# snullv5.net
KiCad netlist of a schematic drawn in EAGLE
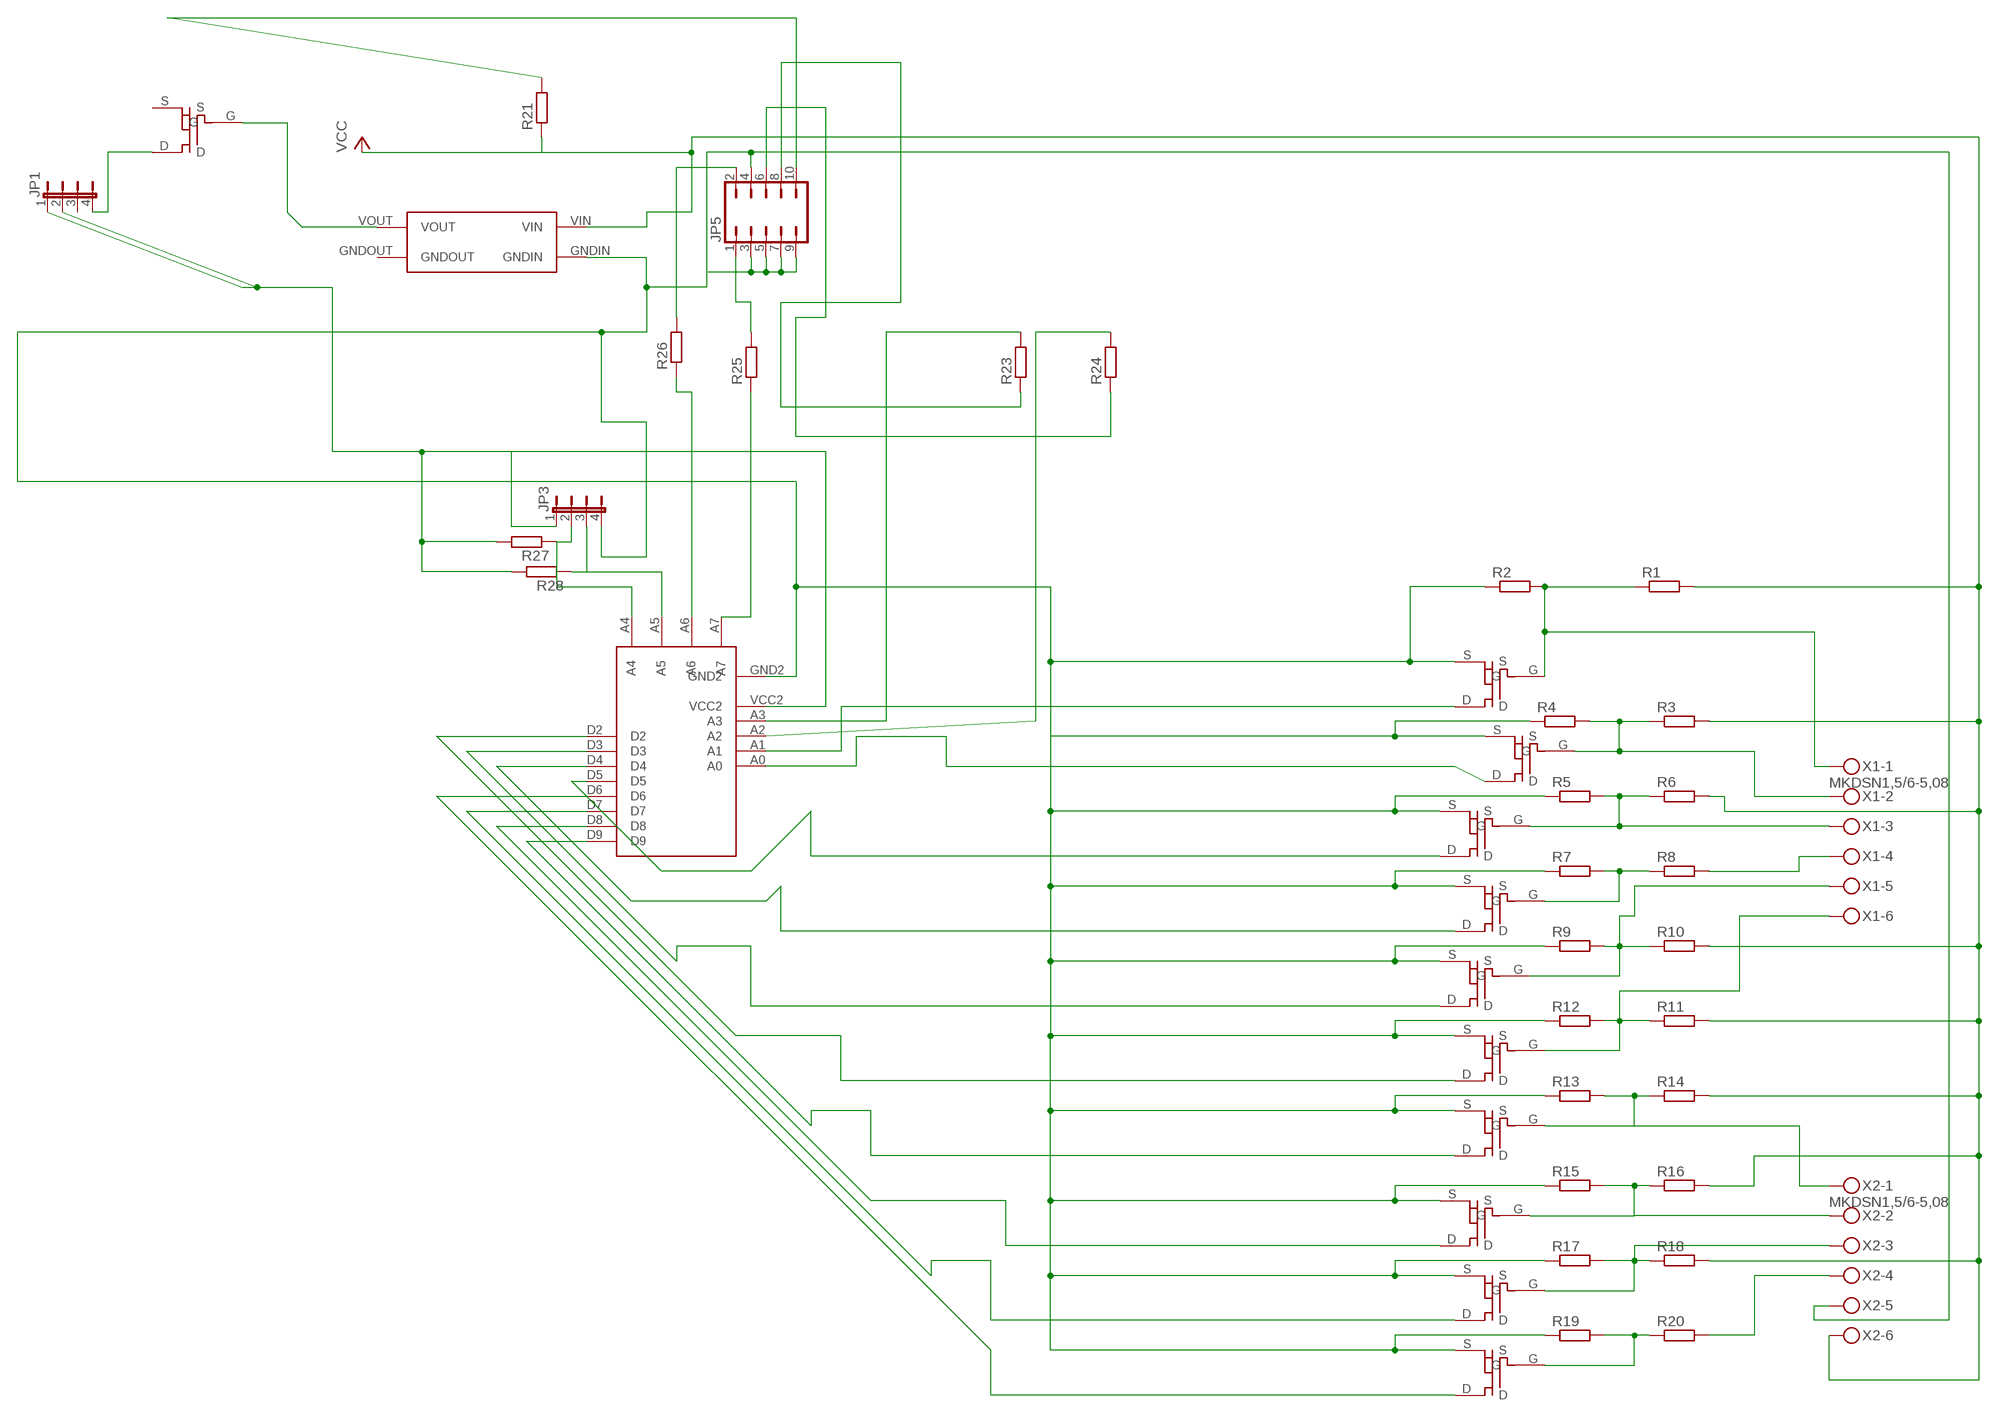
[diagram p0: schematic, sheet 1]

(export (version "E")
  (design (tool "Eeschema 10.0.6"))
  (components
    (comp (ref "JP1")
      (value "JP4E")
      (footprint "eagle-import:JP4")
      (libsource (lib "eagle-import") (part "JP4E"))
    )
    (comp (ref "JP3")
      (value "JP4E")
      (footprint "eagle-import:JP4")
      (libsource (lib "eagle-import") (part "JP4E"))
    )
    (comp (ref "JP5")
      (value "JP5Q")
      (footprint "eagle-import:JP5Q")
      (libsource (lib "eagle-import") (part "JP5Q"))
    )
    (comp (ref "R1")
      (value "R-EU_R0805")
      (footprint "eagle-import:R0805")
      (libsource (lib "eagle-import") (part "R-EU_R0805"))
    )
    (comp (ref "R2")
      (value "R-EU_R0805")
      (footprint "eagle-import:R0805")
      (libsource (lib "eagle-import") (part "R-EU_R0805"))
    )
    (comp (ref "R3")
      (value "R-EU_R0805")
      (footprint "eagle-import:R0805")
      (libsource (lib "eagle-import") (part "R-EU_R0805"))
    )
    (comp (ref "R4")
      (value "R-EU_R0805")
      (footprint "eagle-import:R0805")
      (libsource (lib "eagle-import") (part "R-EU_R0805"))
    )
    (comp (ref "R5")
      (value "R-EU_R0805")
      (footprint "eagle-import:R0805")
      (libsource (lib "eagle-import") (part "R-EU_R0805"))
    )
    (comp (ref "R6")
      (value "R-EU_R0805")
      (footprint "eagle-import:R0805")
      (libsource (lib "eagle-import") (part "R-EU_R0805"))
    )
    (comp (ref "R7")
      (value "R-EU_R0805")
      (footprint "eagle-import:R0805")
      (libsource (lib "eagle-import") (part "R-EU_R0805"))
    )
    (comp (ref "R8")
      (value "R-EU_R0805")
      (footprint "eagle-import:R0805")
      (libsource (lib "eagle-import") (part "R-EU_R0805"))
    )
    (comp (ref "R9")
      (value "R-EU_R0805")
      (footprint "eagle-import:R0805")
      (libsource (lib "eagle-import") (part "R-EU_R0805"))
    )
    (comp (ref "R10")
      (value "R-EU_R0805")
      (footprint "eagle-import:R0805")
      (libsource (lib "eagle-import") (part "R-EU_R0805"))
    )
    (comp (ref "R11")
      (value "R-EU_R0805")
      (footprint "eagle-import:R0805")
      (libsource (lib "eagle-import") (part "R-EU_R0805"))
    )
    (comp (ref "R12")
      (value "R-EU_R0805")
      (footprint "eagle-import:R0805")
      (libsource (lib "eagle-import") (part "R-EU_R0805"))
    )
    (comp (ref "R13")
      (value "R-EU_R0805")
      (footprint "eagle-import:R0805")
      (libsource (lib "eagle-import") (part "R-EU_R0805"))
    )
    (comp (ref "R14")
      (value "R-EU_R0805")
      (footprint "eagle-import:R0805")
      (libsource (lib "eagle-import") (part "R-EU_R0805"))
    )
    (comp (ref "R15")
      (value "R-EU_R0805")
      (footprint "eagle-import:R0805")
      (libsource (lib "eagle-import") (part "R-EU_R0805"))
    )
    (comp (ref "R16")
      (value "R-EU_R0805")
      (footprint "eagle-import:R0805")
      (libsource (lib "eagle-import") (part "R-EU_R0805"))
    )
    (comp (ref "R17")
      (value "R-EU_R0805")
      (footprint "eagle-import:R0805")
      (libsource (lib "eagle-import") (part "R-EU_R0805"))
    )
    (comp (ref "R18")
      (value "R-EU_R0805")
      (footprint "eagle-import:R0805")
      (libsource (lib "eagle-import") (part "R-EU_R0805"))
    )
    (comp (ref "R19")
      (value "R-EU_R0805")
      (footprint "eagle-import:R0805")
      (libsource (lib "eagle-import") (part "R-EU_R0805"))
    )
    (comp (ref "R20")
      (value "R-EU_R0805")
      (footprint "eagle-import:R0805")
      (libsource (lib "eagle-import") (part "R-EU_R0805"))
    )
    (comp (ref "R21")
      (value "R-EU_R0805")
      (footprint "eagle-import:R0805")
      (libsource (lib "eagle-import") (part "R-EU_R0805"))
    )
    (comp (ref "R23")
      (value "R-EU_R0805")
      (footprint "eagle-import:R0805")
      (libsource (lib "eagle-import") (part "R-EU_R0805"))
    )
    (comp (ref "R24")
      (value "R-EU_R0805")
      (footprint "eagle-import:R0805")
      (libsource (lib "eagle-import") (part "R-EU_R0805"))
    )
    (comp (ref "R25")
      (value "R-EU_R0805")
      (footprint "eagle-import:R0805")
      (libsource (lib "eagle-import") (part "R-EU_R0805"))
    )
    (comp (ref "R26")
      (value "R-EU_R0805")
      (footprint "eagle-import:R0805")
      (libsource (lib "eagle-import") (part "R-EU_R0805"))
    )
    (comp (ref "R27")
      (value "R-EU_R0805")
      (footprint "eagle-import:R0805")
      (libsource (lib "eagle-import") (part "R-EU_R0805"))
    )
    (comp (ref "R28")
      (value "R-EU_R0805")
      (footprint "eagle-import:R0805")
      (libsource (lib "eagle-import") (part "R-EU_R0805"))
    )
    (comp (ref "U$1")
      (value "ARDUINOPROMINIREDUCED")
      (footprint "eagle-import:ARDUINOPROMINIREDUCED")
      (libsource (lib "eagle-import") (part "ARDUINOPROMINIREDUCED"))
    )
    (comp (ref "U$2")
      (value "VREGMODULE")
      (footprint "eagle-import:VREGMODULE")
      (libsource (lib "eagle-import") (part "VREGMODULE"))
    )
    (comp (ref "U$3")
      (value "MOSFET-TO236")
      (footprint "eagle-import:MOSFET-TO236")
      (libsource (lib "eagle-import") (part "MOSFET-TO236"))
    )
    (comp (ref "U$4")
      (value "MOSFET-TO236")
      (footprint "eagle-import:MOSFET-TO236")
      (libsource (lib "eagle-import") (part "MOSFET-TO236"))
    )
    (comp (ref "U$5")
      (value "MOSFET-TO236")
      (footprint "eagle-import:MOSFET-TO236")
      (libsource (lib "eagle-import") (part "MOSFET-TO236"))
    )
    (comp (ref "U$6")
      (value "MOSFET-TO236")
      (footprint "eagle-import:MOSFET-TO236")
      (libsource (lib "eagle-import") (part "MOSFET-TO236"))
    )
    (comp (ref "U$7")
      (value "MOSFET-TO236")
      (footprint "eagle-import:MOSFET-TO236")
      (libsource (lib "eagle-import") (part "MOSFET-TO236"))
    )
    (comp (ref "U$8")
      (value "MOSFET-TO236")
      (footprint "eagle-import:MOSFET-TO236")
      (libsource (lib "eagle-import") (part "MOSFET-TO236"))
    )
    (comp (ref "U$9")
      (value "MOSFET-TO236")
      (footprint "eagle-import:MOSFET-TO236")
      (libsource (lib "eagle-import") (part "MOSFET-TO236"))
    )
    (comp (ref "U$10")
      (value "MOSFET-TO236")
      (footprint "eagle-import:MOSFET-TO236")
      (libsource (lib "eagle-import") (part "MOSFET-TO236"))
    )
    (comp (ref "U$11")
      (value "MOSFET-TO236")
      (footprint "eagle-import:MOSFET-TO236")
      (libsource (lib "eagle-import") (part "MOSFET-TO236"))
    )
    (comp (ref "U$12")
      (value "MOSFET-TO236")
      (footprint "eagle-import:MOSFET-TO236")
      (libsource (lib "eagle-import") (part "MOSFET-TO236"))
    )
    (comp (ref "U$13")
      (value "MOSFET-TO236")
      (footprint "eagle-import:MOSFET-TO236")
      (libsource (lib "eagle-import") (part "MOSFET-TO236"))
    )
    (comp (ref "X1")
      (value "MKDSN1,5/6-5,08")
      (footprint "eagle-import:MKDSN1,5_6-5,08")
      (libsource (lib "eagle-import") (part "MKDSN1,5/6-5,08"))
    )
    (comp (ref "X2")
      (value "MKDSN1,5/6-5,08")
      (footprint "eagle-import:MKDSN1,5_6-5,08")
      (libsource (lib "eagle-import") (part "MKDSN1,5/6-5,08"))
    )
  )
  (nets
    (net (code "1") (name "Net-(JP1-Pad1)") (class "Default")
      (node (ref "JP1") (pin "1") (pinfunction "1_1") (pintype "passive"))
      (node (ref "JP1") (pin "2") (pinfunction "2_2") (pintype "passive"))
      (node (ref "JP3") (pin "1") (pinfunction "1_1") (pintype "passive"))
      (node (ref "R27") (pin "2") (pinfunction "2_2") (pintype "passive"))
      (node (ref "R28") (pin "2") (pinfunction "2_2") (pintype "passive"))
      (node (ref "U$1") (pin "VCC2") (pinfunction "VCC2_VCC2") (pintype "bidirectional"))
    )
    (net (code "2") (name "Net-(JP1-Pad4)") (class "Default")
      (node (ref "JP1") (pin "4") (pinfunction "4_4") (pintype "passive"))
      (node (ref "U$13") (pin "D") (pinfunction "D_D") (pintype "bidirectional"))
    )
    (net (code "3") (name "Net-(JP3-Pad2)") (class "Default")
      (node (ref "JP3") (pin "2") (pinfunction "2_2") (pintype "passive"))
      (node (ref "R27") (pin "1") (pinfunction "1_1") (pintype "passive"))
      (node (ref "U$1") (pin "A4") (pinfunction "A4_A4") (pintype "bidirectional"))
    )
    (net (code "4") (name "Net-(JP3-Pad3)") (class "Default")
      (node (ref "JP3") (pin "3") (pinfunction "3_3") (pintype "passive"))
      (node (ref "R28") (pin "1") (pinfunction "1_1") (pintype "passive"))
      (node (ref "U$1") (pin "A5") (pinfunction "A5_A5") (pintype "bidirectional"))
    )
    (net (code "5") (name "Net-(JP5-Pad1)") (class "Default")
      (node (ref "JP5") (pin "1") (pinfunction "1_1") (pintype "passive"))
      (node (ref "R25") (pin "2") (pinfunction "2_2") (pintype "passive"))
    )
    (net (code "6") (name "Net-(JP5-Pad2)") (class "Default")
      (node (ref "JP5") (pin "2") (pinfunction "2_2") (pintype "passive"))
      (node (ref "R26") (pin "2") (pinfunction "2_2") (pintype "passive"))
    )
    (net (code "7") (name "Net-(JP5-Pad6)") (class "Default")
      (node (ref "JP5") (pin "6") (pinfunction "6_6") (pintype "passive"))
      (node (ref "R24") (pin "1") (pinfunction "1_1") (pintype "passive"))
    )
    (net (code "8") (name "Net-(JP5-Pad8)") (class "Default")
      (node (ref "JP5") (pin "8") (pinfunction "8_8") (pintype "passive"))
      (node (ref "R23") (pin "1") (pinfunction "1_1") (pintype "passive"))
    )
    (net (code "9") (name "Net-(JP5-Pad10)") (class "Default")
      (node (ref "JP5") (pin "10") (pinfunction "10_10") (pintype "passive"))
      (node (ref "R21") (pin "2") (pinfunction "2_2") (pintype "passive"))
    )
    (net (code "10") (name "Net-(R7-Pad2)") (class "Default")
      (node (ref "R7") (pin "2") (pinfunction "2_2") (pintype "passive"))
      (node (ref "R8") (pin "1") (pinfunction "1_1") (pintype "passive"))
      (node (ref "U$6") (pin "G") (pinfunction "G_G") (pintype "bidirectional"))
    )
    (net (code "11") (name "Net-(R19-Pad2)") (class "Default")
      (node (ref "R19") (pin "2") (pinfunction "2_2") (pintype "passive"))
      (node (ref "R20") (pin "1") (pinfunction "1_1") (pintype "passive"))
      (node (ref "U$12") (pin "G") (pinfunction "G_G") (pintype "bidirectional"))
    )
    (net (code "12") (name "Net-(R23-Pad2)") (class "Default")
      (node (ref "R23") (pin "2") (pinfunction "2_2") (pintype "passive"))
      (node (ref "U$1") (pin "A3") (pinfunction "A3_A3") (pintype "bidirectional"))
    )
    (net (code "13") (name "Net-(R24-Pad2)") (class "Default")
      (node (ref "R24") (pin "2") (pinfunction "2_2") (pintype "passive"))
      (node (ref "U$1") (pin "A2") (pinfunction "A2_A2") (pintype "bidirectional"))
    )
    (net (code "14") (name "Net-(R25-Pad1)") (class "Default")
      (node (ref "R25") (pin "1") (pinfunction "1_1") (pintype "passive"))
      (node (ref "U$1") (pin "A7") (pinfunction "A7_A7") (pintype "bidirectional"))
    )
    (net (code "15") (name "Net-(R26-Pad1)") (class "Default")
      (node (ref "R26") (pin "1") (pinfunction "1_1") (pintype "passive"))
      (node (ref "U$1") (pin "A6") (pinfunction "A6_A6") (pintype "bidirectional"))
    )
    (net (code "16") (name "Net-(U$1-PadA0)") (class "Default")
      (node (ref "U$1") (pin "A0") (pinfunction "A0_A0") (pintype "bidirectional"))
      (node (ref "U$4") (pin "D") (pinfunction "D_D") (pintype "bidirectional"))
    )
    (net (code "17") (name "Net-(U$1-PadA1)") (class "Default")
      (node (ref "U$1") (pin "A1") (pinfunction "A1_A1") (pintype "bidirectional"))
      (node (ref "U$3") (pin "D") (pinfunction "D_D") (pintype "bidirectional"))
    )
    (net (code "18") (name "Net-(U$1-PadD2)") (class "Default")
      (node (ref "U$1") (pin "D2") (pinfunction "D2_D2") (pintype "bidirectional"))
      (node (ref "U$8") (pin "D") (pinfunction "D_D") (pintype "bidirectional"))
    )
    (net (code "19") (name "Net-(U$1-PadD3)") (class "Default")
      (node (ref "U$1") (pin "D3") (pinfunction "D3_D3") (pintype "bidirectional"))
      (node (ref "U$7") (pin "D") (pinfunction "D_D") (pintype "bidirectional"))
    )
    (net (code "20") (name "Net-(U$1-PadD4)") (class "Default")
      (node (ref "U$1") (pin "D4") (pinfunction "D4_D4") (pintype "bidirectional"))
      (node (ref "U$6") (pin "D") (pinfunction "D_D") (pintype "bidirectional"))
    )
    (net (code "21") (name "Net-(U$1-PadD5)") (class "Default")
      (node (ref "U$1") (pin "D5") (pinfunction "D5_D5") (pintype "bidirectional"))
      (node (ref "U$5") (pin "D") (pinfunction "D_D") (pintype "bidirectional"))
    )
    (net (code "22") (name "Net-(U$1-PadD6)") (class "Default")
      (node (ref "U$1") (pin "D6") (pinfunction "D6_D6") (pintype "bidirectional"))
      (node (ref "U$12") (pin "D") (pinfunction "D_D") (pintype "bidirectional"))
    )
    (net (code "23") (name "Net-(U$1-PadD7)") (class "Default")
      (node (ref "U$1") (pin "D7") (pinfunction "D7_D7") (pintype "bidirectional"))
      (node (ref "U$11") (pin "D") (pinfunction "D_D") (pintype "bidirectional"))
    )
    (net (code "24") (name "Net-(U$1-PadD8)") (class "Default")
      (node (ref "U$1") (pin "D8") (pinfunction "D8_D8") (pintype "bidirectional"))
      (node (ref "U$10") (pin "D") (pinfunction "D_D") (pintype "bidirectional"))
    )
    (net (code "25") (name "Net-(U$1-PadD9)") (class "Default")
      (node (ref "U$1") (pin "D9") (pinfunction "D9_D9") (pintype "bidirectional"))
      (node (ref "U$9") (pin "D") (pinfunction "D_D") (pintype "bidirectional"))
    )
    (net (code "26") (name "Net-(U$13-PadG)") (class "Default")
      (node (ref "U$13") (pin "G") (pinfunction "G_G") (pintype "bidirectional"))
      (node (ref "U$2") (pin "VOUT") (pinfunction "VOUT_VOUT") (pintype "bidirectional"))
    )
    (net (code "27") (name "Net-(X1A-KL)") (class "Default")
      (node (ref "R1") (pin "1") (pinfunction "1_1") (pintype "passive"))
      (node (ref "R2") (pin "2") (pinfunction "2_2") (pintype "passive"))
      (node (ref "U$3") (pin "G") (pinfunction "G_G") (pintype "bidirectional"))
      (node (ref "X1") (pin "1") (pinfunction "KL_1") (pintype "passive"))
    )
    (net (code "28") (name "Net-(X1B-KL)") (class "Default")
      (node (ref "R3") (pin "1") (pinfunction "1_1") (pintype "passive"))
      (node (ref "R4") (pin "2") (pinfunction "2_2") (pintype "passive"))
      (node (ref "U$4") (pin "G") (pinfunction "G_G") (pintype "bidirectional"))
      (node (ref "X1") (pin "2") (pinfunction "KL_2") (pintype "passive"))
    )
    (net (code "29") (name "Net-(X1C-KL)") (class "Default")
      (node (ref "R5") (pin "2") (pinfunction "2_2") (pintype "passive"))
      (node (ref "R6") (pin "1") (pinfunction "1_1") (pintype "passive"))
      (node (ref "U$5") (pin "G") (pinfunction "G_G") (pintype "bidirectional"))
      (node (ref "X1") (pin "3") (pinfunction "KL_3") (pintype "passive"))
    )
    (net (code "30") (name "Net-(X1D-KL)") (class "Default")
      (node (ref "R8") (pin "2") (pinfunction "2_2") (pintype "passive"))
      (node (ref "X1") (pin "4") (pinfunction "KL_4") (pintype "passive"))
    )
    (net (code "31") (name "Net-(X1E-KL)") (class "Default")
      (node (ref "R10") (pin "1") (pinfunction "1_1") (pintype "passive"))
      (node (ref "R9") (pin "2") (pinfunction "2_2") (pintype "passive"))
      (node (ref "U$7") (pin "G") (pinfunction "G_G") (pintype "bidirectional"))
      (node (ref "X1") (pin "5") (pinfunction "KL_5") (pintype "passive"))
    )
    (net (code "32") (name "Net-(X1F-KL)") (class "Default")
      (node (ref "R11") (pin "1") (pinfunction "1_1") (pintype "passive"))
      (node (ref "R12") (pin "2") (pinfunction "2_2") (pintype "passive"))
      (node (ref "U$8") (pin "G") (pinfunction "G_G") (pintype "bidirectional"))
      (node (ref "X1") (pin "6") (pinfunction "KL_6") (pintype "passive"))
    )
    (net (code "33") (name "Net-(X2A-KL)") (class "Default")
      (node (ref "R13") (pin "2") (pinfunction "2_2") (pintype "passive"))
      (node (ref "R14") (pin "1") (pinfunction "1_1") (pintype "passive"))
      (node (ref "U$9") (pin "G") (pinfunction "G_G") (pintype "bidirectional"))
      (node (ref "X2") (pin "1") (pinfunction "KL_1") (pintype "passive"))
    )
    (net (code "34") (name "Net-(X2B-KL)") (class "Default")
      (node (ref "R15") (pin "2") (pinfunction "2_2") (pintype "passive"))
      (node (ref "R16") (pin "1") (pinfunction "1_1") (pintype "passive"))
      (node (ref "U$10") (pin "G") (pinfunction "G_G") (pintype "bidirectional"))
      (node (ref "X2") (pin "2") (pinfunction "KL_2") (pintype "passive"))
    )
    (net (code "35") (name "Net-(X2C-KL)") (class "Default")
      (node (ref "R17") (pin "2") (pinfunction "2_2") (pintype "passive"))
      (node (ref "R18") (pin "1") (pinfunction "1_1") (pintype "passive"))
      (node (ref "U$11") (pin "G") (pinfunction "G_G") (pintype "bidirectional"))
      (node (ref "X2") (pin "3") (pinfunction "KL_3") (pintype "passive"))
    )
    (net (code "36") (name "Net-(X2D-KL)") (class "Default")
      (node (ref "R20") (pin "2") (pinfunction "2_2") (pintype "passive"))
      (node (ref "X2") (pin "4") (pinfunction "KL_4") (pintype "passive"))
    )
    (net (code "37") (name "Net-(X2E-KL)") (class "Default")
      (node (ref "JP3") (pin "4") (pinfunction "4_4") (pintype "passive"))
      (node (ref "JP5") (pin "3") (pinfunction "3_3") (pintype "passive"))
      (node (ref "JP5") (pin "4") (pinfunction "4_4") (pintype "passive"))
      (node (ref "JP5") (pin "5") (pinfunction "5_5") (pintype "passive"))
      (node (ref "JP5") (pin "7") (pinfunction "7_7") (pintype "passive"))
      (node (ref "JP5") (pin "9") (pinfunction "9_9") (pintype "passive"))
      (node (ref "R12") (pin "1") (pinfunction "1_1") (pintype "passive"))
      (node (ref "R13") (pin "1") (pinfunction "1_1") (pintype "passive"))
      (node (ref "R15") (pin "1") (pinfunction "1_1") (pintype "passive"))
      (node (ref "R17") (pin "1") (pinfunction "1_1") (pintype "passive"))
      (node (ref "R19") (pin "1") (pinfunction "1_1") (pintype "passive"))
      (node (ref "R2") (pin "1") (pinfunction "1_1") (pintype "passive"))
      (node (ref "R4") (pin "1") (pinfunction "1_1") (pintype "passive"))
      (node (ref "R5") (pin "1") (pinfunction "1_1") (pintype "passive"))
      (node (ref "R7") (pin "1") (pinfunction "1_1") (pintype "passive"))
      (node (ref "R9") (pin "1") (pinfunction "1_1") (pintype "passive"))
      (node (ref "U$1") (pin "GND2") (pinfunction "GND2_GND2") (pintype "bidirectional"))
      (node (ref "U$10") (pin "S") (pinfunction "S_S") (pintype "bidirectional"))
      (node (ref "U$11") (pin "S") (pinfunction "S_S") (pintype "bidirectional"))
      (node (ref "U$12") (pin "S") (pinfunction "S_S") (pintype "bidirectional"))
      (node (ref "U$2") (pin "GNDIN") (pinfunction "GNDIN_GNDIN") (pintype "bidirectional"))
      (node (ref "U$3") (pin "S") (pinfunction "S_S") (pintype "bidirectional"))
      (node (ref "U$4") (pin "S") (pinfunction "S_S") (pintype "bidirectional"))
      (node (ref "U$5") (pin "S") (pinfunction "S_S") (pintype "bidirectional"))
      (node (ref "U$6") (pin "S") (pinfunction "S_S") (pintype "bidirectional"))
      (node (ref "U$7") (pin "S") (pinfunction "S_S") (pintype "bidirectional"))
      (node (ref "U$8") (pin "S") (pinfunction "S_S") (pintype "bidirectional"))
      (node (ref "U$9") (pin "S") (pinfunction "S_S") (pintype "bidirectional"))
      (node (ref "X2") (pin "5") (pinfunction "KL_5") (pintype "passive"))
    )
    (net (code "38") (name "VCC") (class "Default")
      (node (ref "R1") (pin "2") (pinfunction "2_2") (pintype "passive"))
      (node (ref "R10") (pin "2") (pinfunction "2_2") (pintype "passive"))
      (node (ref "R11") (pin "2") (pinfunction "2_2") (pintype "passive"))
      (node (ref "R14") (pin "2") (pinfunction "2_2") (pintype "passive"))
      (node (ref "R16") (pin "2") (pinfunction "2_2") (pintype "passive"))
      (node (ref "R18") (pin "2") (pinfunction "2_2") (pintype "passive"))
      (node (ref "R21") (pin "1") (pinfunction "1_1") (pintype "passive"))
      (node (ref "R3") (pin "2") (pinfunction "2_2") (pintype "passive"))
      (node (ref "R6") (pin "2") (pinfunction "2_2") (pintype "passive"))
      (node (ref "U$2") (pin "VIN") (pinfunction "VIN_VIN") (pintype "bidirectional"))
      (node (ref "X2") (pin "6") (pinfunction "KL_6") (pintype "passive"))
    )
    (net (code "39") (name "unconnected-(JP1-Pad3)") (class "Default")
      (node (ref "JP1") (pin "3") (pinfunction "3_3") (pintype "passive"))
    )
    (net (code "40") (name "unconnected-(U$2-PadGNDOUT)") (class "Default")
      (node (ref "U$2") (pin "GNDOUT") (pinfunction "GNDOUT_GNDOUT") (pintype "bidirectional"))
    )
    (net (code "41") (name "unconnected-(U$13-PadS)") (class "Default")
      (node (ref "U$13") (pin "S") (pinfunction "S_S") (pintype "bidirectional"))
    )
  )
)
